# Ganganzeige.net
KiCad netlist of a schematic drawn in EAGLE
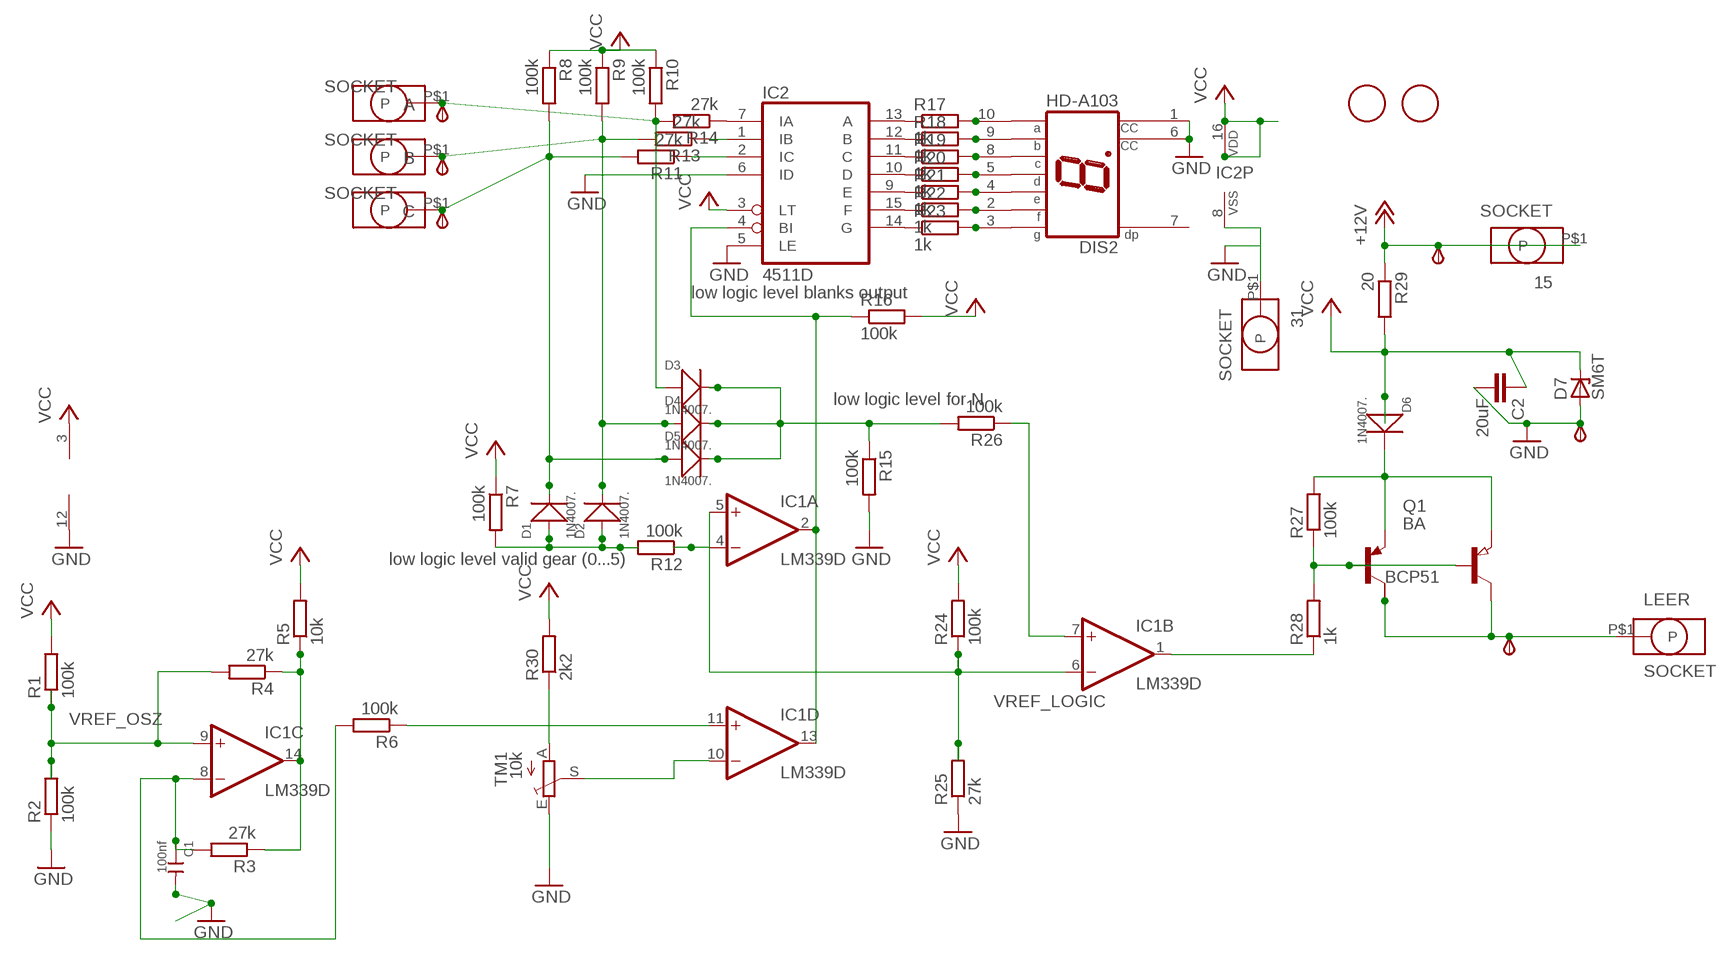
[diagram p0: schematic, sheet 1]

(export (version "E")
  (design (tool "Eeschema 10.0.6"))
  (components
    (comp (ref "15")
      (value "SOCKET")
      (footprint "eagle-import:ID2.5MM")
      (libsource (lib "eagle-import") (part "SOCKET"))
    )
    (comp (ref "15_")
      (value "TPSB2.0")
      (footprint "eagle-import:B2.0")
      (libsource (lib "eagle-import") (part "TPSB2.0"))
    )
    (comp (ref "31")
      (value "SOCKET")
      (footprint "eagle-import:ID2.5MM")
      (libsource (lib "eagle-import") (part "SOCKET"))
    )
    (comp (ref "A")
      (value "SOCKET")
      (footprint "eagle-import:ID2.5MM")
      (libsource (lib "eagle-import") (part "SOCKET"))
    )
    (comp (ref "A_")
      (value "TPSB2.0")
      (footprint "eagle-import:B2.0")
      (libsource (lib "eagle-import") (part "TPSB2.0"))
    )
    (comp (ref "B")
      (value "SOCKET")
      (footprint "eagle-import:ID2.5MM")
      (libsource (lib "eagle-import") (part "SOCKET"))
    )
    (comp (ref "B_")
      (value "TPSB2.0")
      (footprint "eagle-import:B2.0")
      (libsource (lib "eagle-import") (part "TPSB2.0"))
    )
    (comp (ref "C")
      (value "SOCKET")
      (footprint "eagle-import:ID2.5MM")
      (libsource (lib "eagle-import") (part "SOCKET"))
    )
    (comp (ref "C1")
      (value "100nf")
      (footprint "eagle-import:C0805")
      (fields (field (name "MPN") "CC0805KRX7R9BB104"))
      (libsource (lib "eagle-import") (part "CERAMIC-100NF-50V-10%-X7R(0805)"))
    )
    (comp (ref "C2")
      (value "20uF")
      (footprint "eagle-import:C1206K")
      (libsource (lib "eagle-import") (part "C-EUC1206K"))
    )
    (comp (ref "C_")
      (value "TPSB2.0")
      (footprint "eagle-import:B2.0")
      (libsource (lib "eagle-import") (part "TPSB2.0"))
    )
    (comp (ref "D1")
      (value "1N4007.")
      (footprint "eagle-import:DO-214AC")
      (fields (field (name "MPN") "1N4007"))
      (libsource (lib "eagle-import") (part "DIODE-GEN-PURPOSE-1KV-1A(DO-214AC)"))
    )
    (comp (ref "D2")
      (value "1N4007.")
      (footprint "eagle-import:DO-214AC")
      (fields (field (name "MPN") "1N4007"))
      (libsource (lib "eagle-import") (part "DIODE-GEN-PURPOSE-1KV-1A(DO-214AC)"))
    )
    (comp (ref "D3")
      (value "1N4007.")
      (footprint "eagle-import:DO-214AC")
      (fields (field (name "MPN") "1N4007"))
      (libsource (lib "eagle-import") (part "DIODE-GEN-PURPOSE-1KV-1A(DO-214AC)"))
    )
    (comp (ref "D4")
      (value "1N4007.")
      (footprint "eagle-import:DO-214AC")
      (fields (field (name "MPN") "1N4007"))
      (libsource (lib "eagle-import") (part "DIODE-GEN-PURPOSE-1KV-1A(DO-214AC)"))
    )
    (comp (ref "D5")
      (value "1N4007.")
      (footprint "eagle-import:DO-214AC")
      (fields (field (name "MPN") "1N4007"))
      (libsource (lib "eagle-import") (part "DIODE-GEN-PURPOSE-1KV-1A(DO-214AC)"))
    )
    (comp (ref "D6")
      (value "1N4007.")
      (footprint "eagle-import:DO-214AC")
      (fields (field (name "MPN") "1N4007"))
      (libsource (lib "eagle-import") (part "DIODE-GEN-PURPOSE-1KV-1A(DO-214AC)"))
    )
    (comp (ref "D7")
      (value "SM6T")
      (footprint "eagle-import:DO214AA")
      (libsource (lib "eagle-import") (part "SM6T"))
    )
    (comp (ref "DIS2")
      (value "HD-A103")
      (footprint "eagle-import:HDSP-A")
      (libsource (lib "eagle-import") (part "HD-A103"))
    )
    (comp (ref "FID1")
      (value "FIDUCIAL")
      (footprint "eagle-import:FIDUCIAL_1MM")
      (libsource (lib "eagle-import") (part "FIDUCIAL"))
    )
    (comp (ref "FID2")
      (value "FIDUCIAL")
      (footprint "eagle-import:FIDUCIAL_1MM")
      (libsource (lib "eagle-import") (part "FIDUCIAL"))
    )
    (comp (ref "GND_")
      (value "TPSB2.0")
      (footprint "eagle-import:B2.0")
      (libsource (lib "eagle-import") (part "TPSB2.0"))
    )
    (comp (ref "IC1")
      (value "LM339D")
      (footprint "eagle-import:SO14")
      (libsource (lib "eagle-import") (part "LM339D"))
    )
    (comp (ref "IC2")
      (value "4511D")
      (footprint "eagle-import:SO16")
      (libsource (lib "eagle-import") (part "4511D"))
    )
    (comp (ref "LEER")
      (value "SOCKET")
      (footprint "eagle-import:ID2.5MM")
      (libsource (lib "eagle-import") (part "SOCKET"))
    )
    (comp (ref "LEER_")
      (value "TPSB2.0")
      (footprint "eagle-import:B2.0")
      (libsource (lib "eagle-import") (part "TPSB2.0"))
    )
    (comp (ref "Q1")
      (value "BA")
      (footprint "eagle-import:SOT89")
      (libsource (lib "eagle-import") (part "PNP-TRANSISTOR_SOT89"))
    )
    (comp (ref "R1")
      (value "100k")
      (footprint "eagle-import:R0805")
      (libsource (lib "eagle-import") (part "R-EU_R0805"))
    )
    (comp (ref "R2")
      (value "100k")
      (footprint "eagle-import:R0805")
      (libsource (lib "eagle-import") (part "R-EU_R0805"))
    )
    (comp (ref "R3")
      (value "27k")
      (footprint "eagle-import:R0805")
      (libsource (lib "eagle-import") (part "R-EU_R0805"))
    )
    (comp (ref "R4")
      (value "27k")
      (footprint "eagle-import:R0805")
      (libsource (lib "eagle-import") (part "R-EU_R0805"))
    )
    (comp (ref "R5")
      (value "10k")
      (footprint "eagle-import:R0805")
      (libsource (lib "eagle-import") (part "R-EU_R0805"))
    )
    (comp (ref "R6")
      (value "100k")
      (footprint "eagle-import:R0805")
      (libsource (lib "eagle-import") (part "R-EU_R0805"))
    )
    (comp (ref "R7")
      (value "100k")
      (footprint "eagle-import:R0805")
      (libsource (lib "eagle-import") (part "R-EU_R0805"))
    )
    (comp (ref "R8")
      (value "100k")
      (footprint "eagle-import:R0805")
      (libsource (lib "eagle-import") (part "R-EU_R0805"))
    )
    (comp (ref "R9")
      (value "100k")
      (footprint "eagle-import:R0805")
      (libsource (lib "eagle-import") (part "R-EU_R0805"))
    )
    (comp (ref "R10")
      (value "100k")
      (footprint "eagle-import:R0805")
      (libsource (lib "eagle-import") (part "R-EU_R0805"))
    )
    (comp (ref "R11")
      (value "27k")
      (footprint "eagle-import:R0805")
      (libsource (lib "eagle-import") (part "R-EU_R0805"))
    )
    (comp (ref "R12")
      (value "100k")
      (footprint "eagle-import:R0805")
      (libsource (lib "eagle-import") (part "R-EU_R0805"))
    )
    (comp (ref "R13")
      (value "27k")
      (footprint "eagle-import:R0805")
      (libsource (lib "eagle-import") (part "R-EU_R0805"))
    )
    (comp (ref "R14")
      (value "27k")
      (footprint "eagle-import:R0805")
      (libsource (lib "eagle-import") (part "R-EU_R0805"))
    )
    (comp (ref "R15")
      (value "100k")
      (footprint "eagle-import:R0805")
      (libsource (lib "eagle-import") (part "R-EU_R0805"))
    )
    (comp (ref "R16")
      (value "100k")
      (footprint "eagle-import:R0805")
      (libsource (lib "eagle-import") (part "R-EU_R0805"))
    )
    (comp (ref "R17")
      (value "1k")
      (footprint "eagle-import:R0805")
      (libsource (lib "eagle-import") (part "R-EU_R0805"))
    )
    (comp (ref "R18")
      (value "1k")
      (footprint "eagle-import:R0805")
      (libsource (lib "eagle-import") (part "R-EU_R0805"))
    )
    (comp (ref "R19")
      (value "1k")
      (footprint "eagle-import:R0805")
      (libsource (lib "eagle-import") (part "R-EU_R0805"))
    )
    (comp (ref "R20")
      (value "1k")
      (footprint "eagle-import:R0805")
      (libsource (lib "eagle-import") (part "R-EU_R0805"))
    )
    (comp (ref "R21")
      (value "1k")
      (footprint "eagle-import:R0805")
      (libsource (lib "eagle-import") (part "R-EU_R0805"))
    )
    (comp (ref "R22")
      (value "1k")
      (footprint "eagle-import:R0805")
      (libsource (lib "eagle-import") (part "R-EU_R0805"))
    )
    (comp (ref "R23")
      (value "1k")
      (footprint "eagle-import:R0805")
      (libsource (lib "eagle-import") (part "R-EU_R0805"))
    )
    (comp (ref "R24")
      (value "100k")
      (footprint "eagle-import:R0805")
      (libsource (lib "eagle-import") (part "R-EU_R0805"))
    )
    (comp (ref "R25")
      (value "27k")
      (footprint "eagle-import:R0805")
      (libsource (lib "eagle-import") (part "R-EU_R0805"))
    )
    (comp (ref "R26")
      (value "100k")
      (footprint "eagle-import:R0805")
      (libsource (lib "eagle-import") (part "R-EU_R0805"))
    )
    (comp (ref "R27")
      (value "100k")
      (footprint "eagle-import:R0805")
      (libsource (lib "eagle-import") (part "R-EU_R0805"))
    )
    (comp (ref "R28")
      (value "1k")
      (footprint "eagle-import:R0805")
      (libsource (lib "eagle-import") (part "R-EU_R0805"))
    )
    (comp (ref "R29")
      (value "20")
      (footprint "eagle-import:R1206")
      (libsource (lib "eagle-import") (part "R-EU_R1206"))
    )
    (comp (ref "R30")
      (value "2k2")
      (footprint "eagle-import:R0805")
      (libsource (lib "eagle-import") (part "R-EU_R0805"))
    )
    (comp (ref "T")
      (value "BCP53T1")
      (footprint "eagle-import:SOT223")
      (fields (field (name "T") "BCP51"))
      (libsource (lib "eagle-import") (part "BCP53T1"))
    )
    (comp (ref "TM1")
      (value "10k")
      (footprint "eagle-import:S63X")
      (libsource (lib "eagle-import") (part "TRIM_EU-S63X"))
    )
  )
  (nets
    (net (code "1") (name "+12V") (class "Default")
      (node (ref "15") (pin "P$1") (pinfunction "P_P$1") (pintype "bidirectional"))
      (node (ref "15_") (pin "TP") (pinfunction "PP_TP") (pintype "input"))
      (node (ref "R29") (pin "1") (pinfunction "1_1") (pintype "passive"))
    )
    (net (code "2") (name "/VREF_LOGIC") (class "Default")
      (node (ref "IC1") (pin "5") (pinfunction "+IN_5") (pintype "input"))
      (node (ref "IC1") (pin "6") (pinfunction "-IN_6") (pintype "input"))
      (node (ref "R24") (pin "1") (pinfunction "1_1") (pintype "passive"))
      (node (ref "R25") (pin "2") (pinfunction "2_2") (pintype "passive"))
    )
    (net (code "3") (name "/VREF_OSZ") (class "Default")
      (node (ref "IC1") (pin "9") (pinfunction "+IN_9") (pintype "input"))
      (node (ref "R1") (pin "1") (pinfunction "1_1") (pintype "passive"))
      (node (ref "R2") (pin "2") (pinfunction "2_2") (pintype "passive"))
      (node (ref "R4") (pin "2") (pinfunction "2_2") (pintype "passive"))
    )
    (net (code "4") (name "GND") (class "Default")
      (node (ref "31") (pin "P$1") (pinfunction "P_P$1") (pintype "bidirectional"))
      (node (ref "C1") (pin "2") (pinfunction "2_2") (pintype "passive"))
      (node (ref "C2") (pin "2") (pinfunction "2_2") (pintype "passive"))
      (node (ref "D7") (pin "A") (pinfunction "A_A") (pintype "passive"))
      (node (ref "DIS2") (pin "1") (pinfunction "CC_1") (pintype "passive"))
      (node (ref "DIS2") (pin "6") (pinfunction "CC_6") (pintype "passive"))
      (node (ref "GND_") (pin "TP") (pinfunction "PP_TP") (pintype "input"))
      (node (ref "IC1") (pin "12") (pinfunction "GND_12") (pintype "power_in"))
      (node (ref "IC2") (pin "5") (pinfunction "LE_5") (pintype "input"))
      (node (ref "IC2") (pin "6") (pinfunction "ID_6") (pintype "input"))
      (node (ref "IC2") (pin "8") (pinfunction "VSS_8") (pintype "power_in"))
      (node (ref "R15") (pin "2") (pinfunction "2_2") (pintype "passive"))
      (node (ref "R2") (pin "1") (pinfunction "1_1") (pintype "passive"))
      (node (ref "R25") (pin "1") (pinfunction "1_1") (pintype "passive"))
      (node (ref "TM1") (pin "E") (pinfunction "E_E") (pintype "passive"))
    )
    (net (code "5") (name "Net-(A-P)") (class "Default")
      (node (ref "A") (pin "P$1") (pinfunction "P_P$1") (pintype "bidirectional"))
      (node (ref "A_") (pin "TP") (pinfunction "PP_TP") (pintype "input"))
      (node (ref "D3") (pin "1") (pinfunction "+_1") (pintype "passive"))
      (node (ref "R10") (pin "2") (pinfunction "2_2") (pintype "passive"))
      (node (ref "R14") (pin "2") (pinfunction "2_2") (pintype "passive"))
    )
    (net (code "6") (name "Net-(B-P)") (class "Default")
      (node (ref "B") (pin "P$1") (pinfunction "P_P$1") (pintype "bidirectional"))
      (node (ref "B_") (pin "TP") (pinfunction "PP_TP") (pintype "input"))
      (node (ref "D2") (pin "2") (pinfunction "-_2") (pintype "passive"))
      (node (ref "D4") (pin "1") (pinfunction "+_1") (pintype "passive"))
      (node (ref "R13") (pin "2") (pinfunction "2_2") (pintype "passive"))
      (node (ref "R9") (pin "2") (pinfunction "2_2") (pintype "passive"))
    )
    (net (code "7") (name "Net-(C-P)") (class "Default")
      (node (ref "C") (pin "P$1") (pinfunction "P_P$1") (pintype "bidirectional"))
      (node (ref "C_") (pin "TP") (pinfunction "PP_TP") (pintype "input"))
      (node (ref "D1") (pin "2") (pinfunction "-_2") (pintype "passive"))
      (node (ref "D5") (pin "1") (pinfunction "+_1") (pintype "passive"))
      (node (ref "R11") (pin "2") (pinfunction "2_2") (pintype "passive"))
      (node (ref "R8") (pin "2") (pinfunction "2_2") (pintype "passive"))
    )
    (net (code "8") (name "Net-(D1-+)") (class "Default")
      (node (ref "D1") (pin "1") (pinfunction "+_1") (pintype "passive"))
      (node (ref "D2") (pin "1") (pinfunction "+_1") (pintype "passive"))
      (node (ref "R12") (pin "2") (pinfunction "2_2") (pintype "passive"))
      (node (ref "R7") (pin "2") (pinfunction "2_2") (pintype "passive"))
    )
    (net (code "9") (name "Net-(D3--)") (class "Default")
      (node (ref "D3") (pin "2") (pinfunction "-_2") (pintype "passive"))
      (node (ref "D4") (pin "2") (pinfunction "-_2") (pintype "passive"))
      (node (ref "D5") (pin "2") (pinfunction "-_2") (pintype "passive"))
      (node (ref "R15") (pin "1") (pinfunction "1_1") (pintype "passive"))
      (node (ref "R26") (pin "2") (pinfunction "2_2") (pintype "passive"))
    )
    (net (code "10") (name "Net-(D6--)") (class "Default")
      (node (ref "D6") (pin "2") (pinfunction "-_2") (pintype "passive"))
      (node (ref "Q1") (pin "3") (pinfunction "E_3") (pintype "passive"))
      (node (ref "R27") (pin "2") (pinfunction "2_2") (pintype "passive"))
      (node (ref "T") (pin "3") (pinfunction "E_3") (pintype "passive"))
    )
    (net (code "11") (name "Net-(DIS2-A)") (class "Default")
      (node (ref "DIS2") (pin "10") (pinfunction "A_10") (pintype "passive"))
      (node (ref "R17") (pin "2") (pinfunction "2_2") (pintype "passive"))
    )
    (net (code "12") (name "Net-(DIS2-B)") (class "Default")
      (node (ref "DIS2") (pin "9") (pinfunction "B_9") (pintype "passive"))
      (node (ref "R18") (pin "2") (pinfunction "2_2") (pintype "passive"))
    )
    (net (code "13") (name "Net-(DIS2-C)") (class "Default")
      (node (ref "DIS2") (pin "8") (pinfunction "C_8") (pintype "passive"))
      (node (ref "R19") (pin "2") (pinfunction "2_2") (pintype "passive"))
    )
    (net (code "14") (name "Net-(DIS2-D)") (class "Default")
      (node (ref "DIS2") (pin "5") (pinfunction "D_5") (pintype "passive"))
      (node (ref "R20") (pin "2") (pinfunction "2_2") (pintype "passive"))
    )
    (net (code "15") (name "Net-(DIS2-E)") (class "Default")
      (node (ref "DIS2") (pin "4") (pinfunction "E_4") (pintype "passive"))
      (node (ref "R21") (pin "2") (pinfunction "2_2") (pintype "passive"))
    )
    (net (code "16") (name "Net-(DIS2-F)") (class "Default")
      (node (ref "DIS2") (pin "2") (pinfunction "F_2") (pintype "passive"))
      (node (ref "R22") (pin "2") (pinfunction "2_2") (pintype "passive"))
    )
    (net (code "17") (name "Net-(DIS2-G)") (class "Default")
      (node (ref "DIS2") (pin "3") (pinfunction "G_3") (pintype "passive"))
      (node (ref "R23") (pin "2") (pinfunction "2_2") (pintype "passive"))
    )
    (net (code "18") (name "Net-(IC1A--IN)") (class "Default")
      (node (ref "IC1") (pin "4") (pinfunction "-IN_4") (pintype "input"))
      (node (ref "R12") (pin "1") (pinfunction "1_1") (pintype "passive"))
    )
    (net (code "19") (name "Net-(IC1A-OUT)") (class "Default")
      (node (ref "IC1") (pin "13") (pinfunction "OUT_13") (pintype "open_collector"))
      (node (ref "IC1") (pin "2") (pinfunction "OUT_2") (pintype "open_collector"))
      (node (ref "IC2") (pin "4") (pinfunction "BI_4") (pintype "input"))
      (node (ref "R16") (pin "1") (pinfunction "1_1") (pintype "passive"))
    )
    (net (code "20") (name "Net-(IC1B-+IN)") (class "Default")
      (node (ref "IC1") (pin "7") (pinfunction "+IN_7") (pintype "input"))
      (node (ref "R26") (pin "1") (pinfunction "1_1") (pintype "passive"))
    )
    (net (code "21") (name "Net-(IC1B-OUT)") (class "Default")
      (node (ref "IC1") (pin "1") (pinfunction "OUT_1") (pintype "open_collector"))
      (node (ref "R28") (pin "1") (pinfunction "1_1") (pintype "passive"))
    )
    (net (code "22") (name "Net-(IC1C--IN)") (class "Default")
      (node (ref "C1") (pin "1") (pinfunction "1_1") (pintype "passive"))
      (node (ref "IC1") (pin "8") (pinfunction "-IN_8") (pintype "input"))
      (node (ref "R3") (pin "2") (pinfunction "2_2") (pintype "passive"))
      (node (ref "R6") (pin "2") (pinfunction "2_2") (pintype "passive"))
    )
    (net (code "23") (name "Net-(IC1C-OUT)") (class "Default")
      (node (ref "IC1") (pin "14") (pinfunction "OUT_14") (pintype "open_collector"))
      (node (ref "R3") (pin "1") (pinfunction "1_1") (pintype "passive"))
      (node (ref "R4") (pin "1") (pinfunction "1_1") (pintype "passive"))
      (node (ref "R5") (pin "1") (pinfunction "1_1") (pintype "passive"))
    )
    (net (code "24") (name "Net-(IC1D-+IN)") (class "Default")
      (node (ref "IC1") (pin "11") (pinfunction "+IN_11") (pintype "input"))
      (node (ref "R6") (pin "1") (pinfunction "1_1") (pintype "passive"))
    )
    (net (code "25") (name "Net-(IC1D--IN)") (class "Default")
      (node (ref "IC1") (pin "10") (pinfunction "-IN_10") (pintype "input"))
      (node (ref "TM1") (pin "S") (pinfunction "S_S") (pintype "passive"))
    )
    (net (code "26") (name "Net-(IC2A-A)") (class "Default")
      (node (ref "IC2") (pin "13") (pinfunction "A_13") (pintype "output"))
      (node (ref "R17") (pin "1") (pinfunction "1_1") (pintype "passive"))
    )
    (net (code "27") (name "Net-(IC2A-B)") (class "Default")
      (node (ref "IC2") (pin "12") (pinfunction "B_12") (pintype "output"))
      (node (ref "R18") (pin "1") (pinfunction "1_1") (pintype "passive"))
    )
    (net (code "28") (name "Net-(IC2A-C)") (class "Default")
      (node (ref "IC2") (pin "11") (pinfunction "C_11") (pintype "output"))
      (node (ref "R19") (pin "1") (pinfunction "1_1") (pintype "passive"))
    )
    (net (code "29") (name "Net-(IC2A-D)") (class "Default")
      (node (ref "IC2") (pin "10") (pinfunction "D_10") (pintype "output"))
      (node (ref "R20") (pin "1") (pinfunction "1_1") (pintype "passive"))
    )
    (net (code "30") (name "Net-(IC2A-E)") (class "Default")
      (node (ref "IC2") (pin "9") (pinfunction "E_9") (pintype "output"))
      (node (ref "R21") (pin "1") (pinfunction "1_1") (pintype "passive"))
    )
    (net (code "31") (name "Net-(IC2A-F)") (class "Default")
      (node (ref "IC2") (pin "15") (pinfunction "F_15") (pintype "output"))
      (node (ref "R22") (pin "1") (pinfunction "1_1") (pintype "passive"))
    )
    (net (code "32") (name "Net-(IC2A-G)") (class "Default")
      (node (ref "IC2") (pin "14") (pinfunction "G_14") (pintype "output"))
      (node (ref "R23") (pin "1") (pinfunction "1_1") (pintype "passive"))
    )
    (net (code "33") (name "Net-(IC2A-IA)") (class "Default")
      (node (ref "IC2") (pin "7") (pinfunction "IA_7") (pintype "input"))
      (node (ref "R14") (pin "1") (pinfunction "1_1") (pintype "passive"))
    )
    (net (code "34") (name "Net-(IC2A-IB)") (class "Default")
      (node (ref "IC2") (pin "1") (pinfunction "IB_1") (pintype "input"))
      (node (ref "R13") (pin "1") (pinfunction "1_1") (pintype "passive"))
    )
    (net (code "35") (name "Net-(IC2A-IC)") (class "Default")
      (node (ref "IC2") (pin "2") (pinfunction "IC_2") (pintype "input"))
      (node (ref "R11") (pin "1") (pinfunction "1_1") (pintype "passive"))
    )
    (net (code "36") (name "Net-(LEER-P)") (class "Default")
      (node (ref "LEER") (pin "P$1") (pinfunction "P_P$1") (pintype "bidirectional"))
      (node (ref "LEER_") (pin "TP") (pinfunction "PP_TP") (pintype "input"))
      (node (ref "Q1") (pin "2") (pinfunction "C_2") (pintype "passive"))
      (node (ref "T") (pin "2") (pinfunction "C_2") (pintype "passive"))
    )
    (net (code "37") (name "Net-(Q1-B)") (class "Default")
      (node (ref "Q1") (pin "1") (pinfunction "B_1") (pintype "passive"))
      (node (ref "R27") (pin "1") (pinfunction "1_1") (pintype "passive"))
      (node (ref "R28") (pin "2") (pinfunction "2_2") (pintype "passive"))
      (node (ref "T") (pin "1") (pinfunction "B_1") (pintype "passive"))
    )
    (net (code "38") (name "Net-(R30-Pad1)") (class "Default")
      (node (ref "R30") (pin "1") (pinfunction "1_1") (pintype "passive"))
      (node (ref "TM1") (pin "A") (pinfunction "A_A") (pintype "passive"))
    )
    (net (code "39") (name "VCC") (class "Default")
      (node (ref "C2") (pin "1") (pinfunction "1_1") (pintype "passive"))
      (node (ref "D6") (pin "1") (pinfunction "+_1") (pintype "passive"))
      (node (ref "D7") (pin "C") (pinfunction "C_C") (pintype "passive"))
      (node (ref "IC1") (pin "3") (pinfunction "V+_3") (pintype "power_in"))
      (node (ref "IC2") (pin "16") (pinfunction "VDD_16") (pintype "power_in"))
      (node (ref "IC2") (pin "3") (pinfunction "LT_3") (pintype "input"))
      (node (ref "R1") (pin "2") (pinfunction "2_2") (pintype "passive"))
      (node (ref "R10") (pin "1") (pinfunction "1_1") (pintype "passive"))
      (node (ref "R16") (pin "2") (pinfunction "2_2") (pintype "passive"))
      (node (ref "R24") (pin "2") (pinfunction "2_2") (pintype "passive"))
      (node (ref "R29") (pin "2") (pinfunction "2_2") (pintype "passive"))
      (node (ref "R30") (pin "2") (pinfunction "2_2") (pintype "passive"))
      (node (ref "R5") (pin "2") (pinfunction "2_2") (pintype "passive"))
      (node (ref "R7") (pin "1") (pinfunction "1_1") (pintype "passive"))
      (node (ref "R8") (pin "1") (pinfunction "1_1") (pintype "passive"))
      (node (ref "R9") (pin "1") (pinfunction "1_1") (pintype "passive"))
    )
    (net (code "40") (name "unconnected-(DIS2-DP-Pad7)") (class "Default")
      (node (ref "DIS2") (pin "7") (pinfunction "DP_7") (pintype "passive"))
    )
    (net (code "41") (name "unconnected-(T-C{slash}-Pad4)") (class "Default")
      (node (ref "T") (pin "4") (pinfunction "C/_4") (pintype "passive"))
    )
  )
)
